# volume_board_MUSE.net
KiCad netlist of a schematic drawn in EAGLE
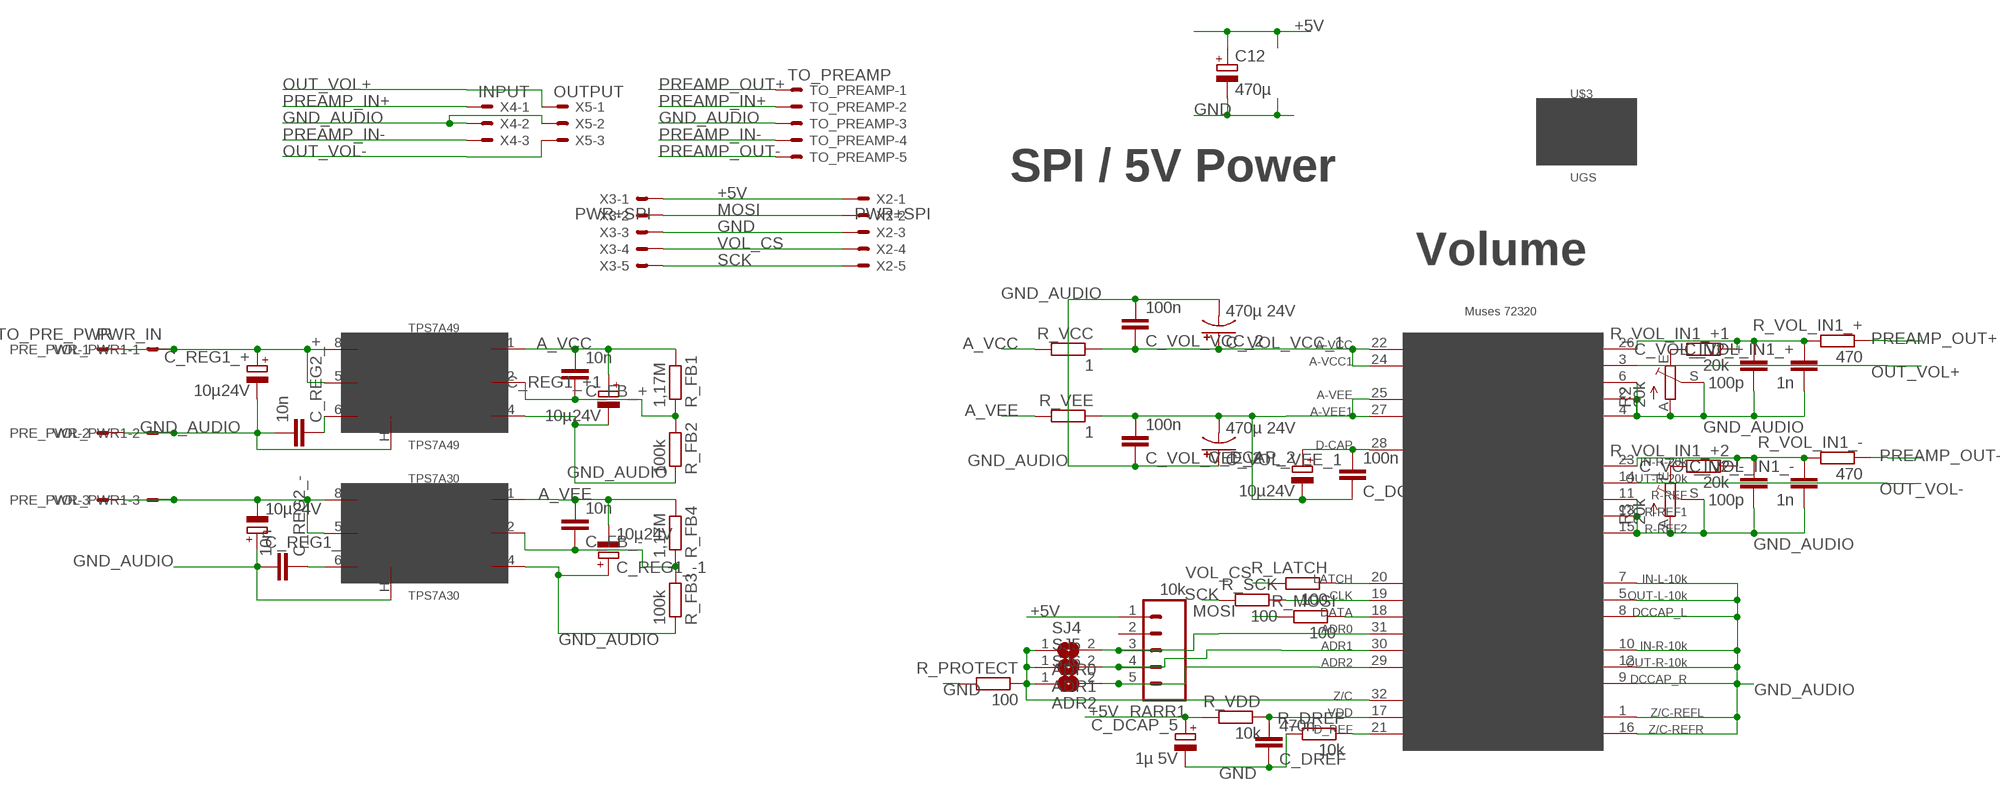
[diagram p0: schematic, sheet 1]

(export (version "E")
  (design (tool "Eeschema 10.0.6"))
  (components
    (comp (ref "C12")
      (value "470µ")
      (footprint "eagle-import:E2,5-6")
      (libsource (lib "eagle-import") (part "CPOL-EUE2.5-6"))
    )
    (comp (ref "C_DCAP_1")
      (value "100n")
      (footprint "eagle-import:C0603")
      (libsource (lib "eagle-import") (part "C-EUC0603"))
    )
    (comp (ref "C_DCAP_2")
      (value "10µ24V")
      (footprint "eagle-import:PANASONIC_C")
      (libsource (lib "eagle-import") (part "CPOL-EUC"))
    )
    (comp (ref "C_DCAP_5")
      (value "1µ 5V")
      (footprint "eagle-import:E1,8-4")
      (libsource (lib "eagle-import") (part "CPOL-EUE1.8-4"))
    )
    (comp (ref "C_DREF")
      (value "470n")
      (footprint "eagle-import:C075-042X103")
      (libsource (lib "eagle-import") (part "C-EU075-042X103"))
    )
    (comp (ref "C_FB_+")
      (value "10n")
      (footprint "eagle-import:C0603")
      (libsource (lib "eagle-import") (part "C-EUC0603"))
    )
    (comp (ref "C_FB_-")
      (value "10n")
      (footprint "eagle-import:C0603")
      (libsource (lib "eagle-import") (part "C-EUC0603"))
    )
    (comp (ref "C_REG1_+")
      (value "10µ24V")
      (footprint "eagle-import:PANASONIC_C")
      (libsource (lib "eagle-import") (part "CPOL-EUC"))
    )
    (comp (ref "C_REG1_+1")
      (value "10µ24V")
      (footprint "eagle-import:PANASONIC_C")
      (libsource (lib "eagle-import") (part "CPOL-EUC"))
    )
    (comp (ref "C_REG1_-")
      (value "10µ24V")
      (footprint "eagle-import:PANASONIC_C")
      (libsource (lib "eagle-import") (part "CPOL-EUC"))
    )
    (comp (ref "C_REG1_-1")
      (value "10µ24V")
      (footprint "eagle-import:PANASONIC_C")
      (libsource (lib "eagle-import") (part "CPOL-EUC"))
    )
    (comp (ref "C_REG2_+")
      (value "10n")
      (footprint "eagle-import:C0603")
      (libsource (lib "eagle-import") (part "C-EUC0603"))
    )
    (comp (ref "C_REG2_-")
      (value "10n")
      (footprint "eagle-import:C0603")
      (libsource (lib "eagle-import") (part "C-EUC0603"))
    )
    (comp (ref "C_VOL_IN1_+")
      (value "1n")
      (footprint "eagle-import:C102-043X133")
      (libsource (lib "eagle-import") (part "C-EU102-043X133"))
    )
    (comp (ref "C_VOL_IN1_-")
      (value "1n")
      (footprint "eagle-import:C102-043X133")
      (libsource (lib "eagle-import") (part "C-EU102-043X133"))
    )
    (comp (ref "C_VOL_IN2_+")
      (value "100p")
      (footprint "eagle-import:C075-032X103")
      (libsource (lib "eagle-import") (part "C-EU075-032X103"))
    )
    (comp (ref "C_VOL_IN2_-")
      (value "100p")
      (footprint "eagle-import:C075-032X103")
      (libsource (lib "eagle-import") (part "C-EU075-032X103"))
    )
    (comp (ref "C_VOL_VCC_1")
      (value "470µ 24V")
      (footprint "eagle-import:PANASONIC_H13")
      (libsource (lib "eagle-import") (part "CAP_POLH13"))
    )
    (comp (ref "C_VOL_VCC_2")
      (value "100n")
      (footprint "eagle-import:C0603")
      (libsource (lib "eagle-import") (part "C-EUC0603"))
    )
    (comp (ref "C_VOL_VEE_1")
      (value "470µ 24V")
      (footprint "eagle-import:PANASONIC_H13")
      (libsource (lib "eagle-import") (part "CAP_POLH13"))
    )
    (comp (ref "C_VOL_VEE_2")
      (value "100n")
      (footprint "eagle-import:C0603")
      (libsource (lib "eagle-import") (part "C-EUC0603"))
    )
    (comp (ref "PRE_PWR")
      (value "TO_PRE_PWR")
      (footprint "eagle-import:70543-03")
      (libsource (lib "eagle-import") (part "C-GRID-03-70543"))
    )
    (comp (ref "R2")
      (value "20k")
      (footprint "eagle-import:RJ9W")
      (libsource (lib "eagle-import") (part "TRIM_EU-RJ9W"))
    )
    (comp (ref "R3")
      (value "20k")
      (footprint "eagle-import:RJ9W")
      (libsource (lib "eagle-import") (part "TRIM_EU-RJ9W"))
    )
    (comp (ref "RARR1")
      (value "10k")
      (footprint "eagle-import:1X05")
      (libsource (lib "eagle-import") (part "M05PTH"))
    )
    (comp (ref "R_DREF")
      (value "10k")
      (footprint "eagle-import:0207_7")
      (libsource (lib "eagle-import") (part "R-EU_0207/7"))
    )
    (comp (ref "R_FB1")
      (value "1,17M")
      (footprint "eagle-import:0207_7")
      (libsource (lib "eagle-import") (part "R-EU_0207/7"))
    )
    (comp (ref "R_FB2")
      (value "100k")
      (footprint "eagle-import:0207_7")
      (libsource (lib "eagle-import") (part "R-EU_0207/7"))
    )
    (comp (ref "R_FB3")
      (value "100k")
      (footprint "eagle-import:0207_7")
      (libsource (lib "eagle-import") (part "R-EU_0207/7"))
    )
    (comp (ref "R_FB4")
      (value "1,17M")
      (footprint "eagle-import:0207_7")
      (libsource (lib "eagle-import") (part "R-EU_0207/7"))
    )
    (comp (ref "R_LATCH")
      (value "100")
      (footprint "eagle-import:0207_7")
      (libsource (lib "eagle-import") (part "R-EU_0207/7"))
    )
    (comp (ref "R_MOSI")
      (value "100")
      (footprint "eagle-import:0207_7")
      (libsource (lib "eagle-import") (part "R-EU_0207/7"))
    )
    (comp (ref "R_PROTECT")
      (value "100")
      (footprint "eagle-import:0207_7")
      (libsource (lib "eagle-import") (part "R-EU_0207/7"))
    )
    (comp (ref "R_SCK")
      (value "100")
      (footprint "eagle-import:0207_7")
      (libsource (lib "eagle-import") (part "R-EU_0207/7"))
    )
    (comp (ref "R_VCC")
      (value "1")
      (footprint "eagle-import:0207_7")
      (libsource (lib "eagle-import") (part "R-EU_0207/7"))
    )
    (comp (ref "R_VDD")
      (value "10k")
      (footprint "eagle-import:0207_7")
      (libsource (lib "eagle-import") (part "R-EU_0207/7"))
    )
    (comp (ref "R_VEE")
      (value "1")
      (footprint "eagle-import:0207_7")
      (libsource (lib "eagle-import") (part "R-EU_0207/7"))
    )
    (comp (ref "R_VOL_IN1_+")
      (value "470")
      (footprint "eagle-import:0207_10")
      (libsource (lib "eagle-import") (part "R-EU_0207/10"))
    )
    (comp (ref "R_VOL_IN1_+1")
      (value "20k")
      (footprint "eagle-import:0207_7")
      (libsource (lib "eagle-import") (part "R-EU_0207/7"))
    )
    (comp (ref "R_VOL_IN1_+2")
      (value "20k")
      (footprint "eagle-import:0207_7")
      (libsource (lib "eagle-import") (part "R-EU_0207/7"))
    )
    (comp (ref "R_VOL_IN1_-")
      (value "470")
      (footprint "eagle-import:0207_10")
      (libsource (lib "eagle-import") (part "R-EU_0207/10"))
    )
    (comp (ref "SJ4")
      (value "ADR0")
      (footprint "eagle-import:SJ")
      (libsource (lib "eagle-import") (part "SJ"))
    )
    (comp (ref "SJ5")
      (value "ADR1")
      (footprint "eagle-import:SJ")
      (libsource (lib "eagle-import") (part "SJ"))
    )
    (comp (ref "SJ6")
      (value "ADR2")
      (footprint "eagle-import:SJ")
      (libsource (lib "eagle-import") (part "SJ"))
    )
    (comp (ref "TO_PREAMP")
      (value "TO_PREAMP")
      (footprint "eagle-import:70543-05")
      (libsource (lib "eagle-import") (part "C-GRID-05-70543"))
    )
    (comp (ref "TPS7A30")
      (value "TPS7A30")
      (footprint "eagle-import:MSOP8")
      (libsource (lib "eagle-import") (part "TPS7A49+36V150MA_REG"))
    )
    (comp (ref "TPS7A49")
      (value "TPS7A49")
      (footprint "eagle-import:MSOP8")
      (libsource (lib "eagle-import") (part "TPS7A49+36V150MA_REG"))
    )
    (comp (ref "U$1")
      (value "MUSES72320")
      (footprint "eagle-import:SSOP32")
      (libsource (lib "eagle-import") (part "MUSES72320"))
    )
    (comp (ref "U$3")
      (value "UGS")
      (footprint "eagle-import:UGS")
      (libsource (lib "eagle-import") (part "UGS"))
    )
    (comp (ref "VOL_PWR1")
      (value "PWR_IN")
      (footprint "eagle-import:70543-03")
      (libsource (lib "eagle-import") (part "C-GRID-03-70543"))
    )
    (comp (ref "X2")
      (value "PWR+SPI")
      (footprint "eagle-import:70543-05")
      (libsource (lib "eagle-import") (part "C-GRID-05-70543"))
    )
    (comp (ref "X3")
      (value "PWR+SPI")
      (footprint "eagle-import:70543-05")
      (libsource (lib "eagle-import") (part "C-GRID-05-70543"))
    )
    (comp (ref "X4")
      (value "INPUT")
      (footprint "eagle-import:70543-03")
      (libsource (lib "eagle-import") (part "C-GRID-03-70543"))
    )
    (comp (ref "X5")
      (value "OUTPUT")
      (footprint "eagle-import:70543-03")
      (libsource (lib "eagle-import") (part "C-GRID-03-70543"))
    )
  )
  (nets
    (net (code "1") (name "/+5V") (class "Default")
      (node (ref "C12") (pin "+") (pinfunction "+_+") (pintype "passive"))
      (node (ref "C_DCAP_5") (pin "+") (pinfunction "+_+") (pintype "passive"))
      (node (ref "RARR1") (pin "1") (pinfunction "1_1") (pintype "passive"))
      (node (ref "R_VDD") (pin "2") (pinfunction "2_2") (pintype "passive"))
      (node (ref "X2") (pin "1") (pinfunction "S_1") (pintype "passive"))
      (node (ref "X3") (pin "1") (pinfunction "S_1") (pintype "passive"))
    )
    (net (code "2") (name "/A_VCC") (class "Default")
      (node (ref "C_FB_+") (pin "2") (pinfunction "2_2") (pintype "passive"))
      (node (ref "C_REG1_+1") (pin "+") (pinfunction "+_+") (pintype "passive"))
      (node (ref "R_FB1") (pin "2") (pinfunction "2_2") (pintype "passive"))
      (node (ref "R_VCC") (pin "2") (pinfunction "2_2") (pintype "passive"))
      (node (ref "TPS7A49") (pin "1") (pinfunction "OUT_1") (pintype "bidirectional"))
    )
    (net (code "3") (name "/A_VEE") (class "Default")
      (node (ref "C_FB_-") (pin "2") (pinfunction "2_2") (pintype "passive"))
      (node (ref "C_REG1_-1") (pin "-") (pinfunction "-_-") (pintype "passive"))
      (node (ref "R_FB4") (pin "2") (pinfunction "2_2") (pintype "passive"))
      (node (ref "R_VEE") (pin "2") (pinfunction "2_2") (pintype "passive"))
      (node (ref "TPS7A30") (pin "1") (pinfunction "OUT_1") (pintype "bidirectional"))
    )
    (net (code "4") (name "/GND") (class "Default")
      (node (ref "C12") (pin "-") (pinfunction "-_-") (pintype "passive"))
      (node (ref "C_DCAP_5") (pin "-") (pinfunction "-_-") (pintype "passive"))
      (node (ref "C_DREF") (pin "1") (pinfunction "1_1") (pintype "passive"))
      (node (ref "R_DREF") (pin "2") (pinfunction "2_2") (pintype "passive"))
      (node (ref "R_PROTECT") (pin "2") (pinfunction "2_2") (pintype "passive"))
      (node (ref "X2") (pin "3") (pinfunction "S_3") (pintype "passive"))
      (node (ref "X3") (pin "3") (pinfunction "S_3") (pintype "passive"))
    )
    (net (code "5") (name "/GND_AUDIO") (class "Default")
      (node (ref "C_REG1_+") (pin "-") (pinfunction "-_-") (pintype "passive"))
      (node (ref "C_REG1_+1") (pin "-") (pinfunction "-_-") (pintype "passive"))
      (node (ref "C_REG1_-") (pin "+") (pinfunction "+_+") (pintype "passive"))
      (node (ref "C_REG1_-1") (pin "+") (pinfunction "+_+") (pintype "passive"))
      (node (ref "C_REG2_+") (pin "2") (pinfunction "2_2") (pintype "passive"))
      (node (ref "C_REG2_-") (pin "2") (pinfunction "2_2") (pintype "passive"))
      (node (ref "C_VOL_IN1_+") (pin "2") (pinfunction "2_2") (pintype "passive"))
      (node (ref "C_VOL_IN1_-") (pin "2") (pinfunction "2_2") (pintype "passive"))
      (node (ref "C_VOL_IN2_+") (pin "2") (pinfunction "2_2") (pintype "passive"))
      (node (ref "C_VOL_IN2_-") (pin "2") (pinfunction "2_2") (pintype "passive"))
      (node (ref "C_VOL_VCC_1") (pin "-") (pinfunction "-_-") (pintype "passive"))
      (node (ref "C_VOL_VCC_2") (pin "2") (pinfunction "2_2") (pintype "passive"))
      (node (ref "C_VOL_VEE_1") (pin "+") (pinfunction "+_+") (pintype "passive"))
      (node (ref "C_VOL_VEE_2") (pin "1") (pinfunction "1_1") (pintype "passive"))
      (node (ref "PRE_PWR") (pin "2") (pinfunction "S_2") (pintype "passive"))
      (node (ref "R2") (pin "A") (pinfunction "A_A") (pintype "passive"))
      (node (ref "R2") (pin "S") (pinfunction "S_S") (pintype "passive"))
      (node (ref "R3") (pin "A") (pinfunction "A_A") (pintype "passive"))
      (node (ref "R3") (pin "S") (pinfunction "S_S") (pintype "passive"))
      (node (ref "R_FB2") (pin "1") (pinfunction "1_1") (pintype "passive"))
      (node (ref "R_FB3") (pin "1") (pinfunction "1_1") (pintype "passive"))
      (node (ref "TO_PREAMP") (pin "3") (pinfunction "S_3") (pintype "passive"))
      (node (ref "TPS7A30") (pin "4") (pinfunction "GND_4") (pintype "bidirectional"))
      (node (ref "TPS7A30") (pin "H") (pinfunction "H_H") (pintype "bidirectional"))
      (node (ref "TPS7A49") (pin "4") (pinfunction "GND_4") (pintype "bidirectional"))
      (node (ref "TPS7A49") (pin "H") (pinfunction "H_H") (pintype "bidirectional"))
      (node (ref "U$1") (pin "1") (pinfunction "P$1_1") (pintype "bidirectional"))
      (node (ref "U$1") (pin "10") (pinfunction "P$10_10") (pintype "bidirectional"))
      (node (ref "U$1") (pin "11") (pinfunction "P$11_11") (pintype "bidirectional"))
      (node (ref "U$1") (pin "12") (pinfunction "P$12_12") (pintype "bidirectional"))
      (node (ref "U$1") (pin "13") (pinfunction "P$13_13") (pintype "bidirectional"))
      (node (ref "U$1") (pin "15") (pinfunction "P$15_15") (pintype "bidirectional"))
      (node (ref "U$1") (pin "16") (pinfunction "P$16_16") (pintype "bidirectional"))
      (node (ref "U$1") (pin "2") (pinfunction "P$2_2") (pintype "bidirectional"))
      (node (ref "U$1") (pin "4") (pinfunction "P$4_4") (pintype "bidirectional"))
      (node (ref "U$1") (pin "5") (pinfunction "P$5_5") (pintype "bidirectional"))
      (node (ref "U$1") (pin "6") (pinfunction "P$6_6") (pintype "bidirectional"))
      (node (ref "U$1") (pin "7") (pinfunction "P$7_7") (pintype "bidirectional"))
      (node (ref "U$1") (pin "8") (pinfunction "P$8_8") (pintype "bidirectional"))
      (node (ref "U$1") (pin "9") (pinfunction "P$9_9") (pintype "bidirectional"))
      (node (ref "VOL_PWR1") (pin "2") (pinfunction "S_2") (pintype "passive"))
      (node (ref "X4") (pin "2") (pinfunction "S_2") (pintype "passive"))
      (node (ref "X5") (pin "2") (pinfunction "S_2") (pintype "passive"))
    )
    (net (code "6") (name "/MOSI") (class "Default")
      (node (ref "R_MOSI") (pin "2") (pinfunction "2_2") (pintype "passive"))
      (node (ref "X2") (pin "2") (pinfunction "S_2") (pintype "passive"))
      (node (ref "X3") (pin "2") (pinfunction "S_2") (pintype "passive"))
    )
    (net (code "7") (name "/OUT_VOL+") (class "Default")
      (node (ref "U$1") (pin "3") (pinfunction "P$3_3") (pintype "bidirectional"))
      (node (ref "X5") (pin "1") (pinfunction "S_1") (pintype "passive"))
    )
    (net (code "8") (name "/OUT_VOL-") (class "Default")
      (node (ref "U$1") (pin "14") (pinfunction "P$14_14") (pintype "bidirectional"))
      (node (ref "X5") (pin "3") (pinfunction "S_3") (pintype "passive"))
    )
    (net (code "9") (name "/PREAMP_IN+") (class "Default")
      (node (ref "TO_PREAMP") (pin "2") (pinfunction "S_2") (pintype "passive"))
      (node (ref "X4") (pin "1") (pinfunction "S_1") (pintype "passive"))
    )
    (net (code "10") (name "/PREAMP_IN-") (class "Default")
      (node (ref "TO_PREAMP") (pin "4") (pinfunction "S_4") (pintype "passive"))
      (node (ref "X4") (pin "3") (pinfunction "S_3") (pintype "passive"))
    )
    (net (code "11") (name "/PREAMP_OUT+") (class "Default")
      (node (ref "R_VOL_IN1_+") (pin "1") (pinfunction "1_1") (pintype "passive"))
      (node (ref "TO_PREAMP") (pin "1") (pinfunction "S_1") (pintype "passive"))
    )
    (net (code "12") (name "/PREAMP_OUT-") (class "Default")
      (node (ref "R_VOL_IN1_-") (pin "1") (pinfunction "1_1") (pintype "passive"))
      (node (ref "TO_PREAMP") (pin "5") (pinfunction "S_5") (pintype "passive"))
    )
    (net (code "13") (name "/SCK") (class "Default")
      (node (ref "R_SCK") (pin "2") (pinfunction "2_2") (pintype "passive"))
      (node (ref "X2") (pin "5") (pinfunction "S_5") (pintype "passive"))
      (node (ref "X3") (pin "5") (pinfunction "S_5") (pintype "passive"))
    )
    (net (code "14") (name "/VOL_CS") (class "Default")
      (node (ref "R_LATCH") (pin "2") (pinfunction "2_2") (pintype "passive"))
      (node (ref "X2") (pin "4") (pinfunction "S_4") (pintype "passive"))
      (node (ref "X3") (pin "4") (pinfunction "S_4") (pintype "passive"))
    )
    (net (code "15") (name "Net-(PRE_PWRA-S)") (class "Default")
      (node (ref "C_REG1_+") (pin "+") (pinfunction "+_+") (pintype "passive"))
      (node (ref "PRE_PWR") (pin "1") (pinfunction "S_1") (pintype "passive"))
      (node (ref "TPS7A49") (pin "5") (pinfunction "EN_5") (pintype "bidirectional"))
      (node (ref "TPS7A49") (pin "8") (pinfunction "IN_8") (pintype "bidirectional"))
      (node (ref "VOL_PWR1") (pin "1") (pinfunction "S_1") (pintype "passive"))
    )
    (net (code "16") (name "Net-(PRE_PWRC-S)") (class "Default")
      (node (ref "C_REG1_-") (pin "-") (pinfunction "-_-") (pintype "passive"))
      (node (ref "PRE_PWR") (pin "3") (pinfunction "S_3") (pintype "passive"))
      (node (ref "TPS7A30") (pin "5") (pinfunction "EN_5") (pintype "bidirectional"))
      (node (ref "TPS7A30") (pin "8") (pinfunction "IN_8") (pintype "bidirectional"))
      (node (ref "VOL_PWR1") (pin "3") (pinfunction "S_3") (pintype "passive"))
    )
    (net (code "17") (name "Net-(R2-PadE)") (class "Default")
      (node (ref "R2") (pin "E") (pinfunction "E_E") (pintype "passive"))
      (node (ref "R_VOL_IN1_+1") (pin "2") (pinfunction "2_2") (pintype "passive"))
    )
    (net (code "18") (name "Net-(R3-PadE)") (class "Default")
      (node (ref "R3") (pin "E") (pinfunction "E_E") (pintype "passive"))
      (node (ref "R_VOL_IN1_+2") (pin "2") (pinfunction "2_2") (pintype "passive"))
    )
    (net (code "19") (name "Net-(TPS7A30-FB)") (class "Default")
      (node (ref "C_FB_-") (pin "1") (pinfunction "1_1") (pintype "passive"))
      (node (ref "R_FB3") (pin "2") (pinfunction "2_2") (pintype "passive"))
      (node (ref "R_FB4") (pin "1") (pinfunction "1_1") (pintype "passive"))
      (node (ref "TPS7A30") (pin "2") (pinfunction "FB_2") (pintype "bidirectional"))
    )
    (net (code "20") (name "Net-(TPS7A30-NR{slash}SS)") (class "Default")
      (node (ref "C_REG2_-") (pin "1") (pinfunction "1_1") (pintype "passive"))
      (node (ref "TPS7A30") (pin "6") (pinfunction "NR/SS_6") (pintype "bidirectional"))
    )
    (net (code "21") (name "Net-(TPS7A49-FB)") (class "Default")
      (node (ref "C_FB_+") (pin "1") (pinfunction "1_1") (pintype "passive"))
      (node (ref "R_FB1") (pin "1") (pinfunction "1_1") (pintype "passive"))
      (node (ref "R_FB2") (pin "2") (pinfunction "2_2") (pintype "passive"))
      (node (ref "TPS7A49") (pin "2") (pinfunction "FB_2") (pintype "bidirectional"))
    )
    (net (code "22") (name "Net-(TPS7A49-NR{slash}SS)") (class "Default")
      (node (ref "C_REG2_+") (pin "1") (pinfunction "1_1") (pintype "passive"))
      (node (ref "TPS7A49") (pin "6") (pinfunction "NR/SS_6") (pintype "bidirectional"))
    )
    (net (code "23") (name "Net-(U$1-P$17)") (class "Default")
      (node (ref "C_DREF") (pin "2") (pinfunction "2_2") (pintype "passive"))
      (node (ref "R_VDD") (pin "1") (pinfunction "1_1") (pintype "passive"))
      (node (ref "U$1") (pin "17") (pinfunction "P$17_17") (pintype "bidirectional"))
    )
    (net (code "24") (name "Net-(U$1-P$18)") (class "Default")
      (node (ref "R_MOSI") (pin "1") (pinfunction "1_1") (pintype "passive"))
      (node (ref "U$1") (pin "18") (pinfunction "P$18_18") (pintype "bidirectional"))
    )
    (net (code "25") (name "Net-(U$1-P$19)") (class "Default")
      (node (ref "R_SCK") (pin "1") (pinfunction "1_1") (pintype "passive"))
      (node (ref "U$1") (pin "19") (pinfunction "P$19_19") (pintype "bidirectional"))
    )
    (net (code "26") (name "Net-(U$1-P$20)") (class "Default")
      (node (ref "R_LATCH") (pin "1") (pinfunction "1_1") (pintype "passive"))
      (node (ref "U$1") (pin "20") (pinfunction "P$20_20") (pintype "bidirectional"))
    )
    (net (code "27") (name "Net-(U$1-P$21)") (class "Default")
      (node (ref "R_DREF") (pin "1") (pinfunction "1_1") (pintype "passive"))
      (node (ref "U$1") (pin "21") (pinfunction "P$21_21") (pintype "bidirectional"))
    )
    (net (code "28") (name "Net-(U$1-P$22)") (class "Default")
      (node (ref "C_VOL_VCC_1") (pin "+") (pinfunction "+_+") (pintype "passive"))
      (node (ref "C_VOL_VCC_2") (pin "1") (pinfunction "1_1") (pintype "passive"))
      (node (ref "R_VCC") (pin "1") (pinfunction "1_1") (pintype "passive"))
      (node (ref "U$1") (pin "22") (pinfunction "P$22_22") (pintype "bidirectional"))
      (node (ref "U$1") (pin "24") (pinfunction "P$24_24") (pintype "bidirectional"))
    )
    (net (code "29") (name "Net-(U$1-P$23)") (class "Default")
      (node (ref "C_VOL_IN1_-") (pin "1") (pinfunction "1_1") (pintype "passive"))
      (node (ref "C_VOL_IN2_-") (pin "1") (pinfunction "1_1") (pintype "passive"))
      (node (ref "R_VOL_IN1_+2") (pin "1") (pinfunction "1_1") (pintype "passive"))
      (node (ref "R_VOL_IN1_-") (pin "2") (pinfunction "2_2") (pintype "passive"))
      (node (ref "U$1") (pin "23") (pinfunction "P$23_23") (pintype "bidirectional"))
    )
    (net (code "30") (name "Net-(U$1-P$25)") (class "Default")
      (node (ref "C_DCAP_1") (pin "1") (pinfunction "1_1") (pintype "passive"))
      (node (ref "C_DCAP_2") (pin "-") (pinfunction "-_-") (pintype "passive"))
      (node (ref "C_VOL_VEE_1") (pin "-") (pinfunction "-_-") (pintype "passive"))
      (node (ref "C_VOL_VEE_2") (pin "2") (pinfunction "2_2") (pintype "passive"))
      (node (ref "R_VEE") (pin "1") (pinfunction "1_1") (pintype "passive"))
      (node (ref "U$1") (pin "25") (pinfunction "P$25_25") (pintype "bidirectional"))
      (node (ref "U$1") (pin "27") (pinfunction "P$27_27") (pintype "bidirectional"))
    )
    (net (code "31") (name "Net-(U$1-P$26)") (class "Default")
      (node (ref "C_VOL_IN1_+") (pin "1") (pinfunction "1_1") (pintype "passive"))
      (node (ref "C_VOL_IN2_+") (pin "1") (pinfunction "1_1") (pintype "passive"))
      (node (ref "R_VOL_IN1_+") (pin "2") (pinfunction "2_2") (pintype "passive"))
      (node (ref "R_VOL_IN1_+1") (pin "1") (pinfunction "1_1") (pintype "passive"))
      (node (ref "U$1") (pin "26") (pinfunction "P$26_26") (pintype "bidirectional"))
    )
    (net (code "32") (name "Net-(U$1-P$28)") (class "Default")
      (node (ref "C_DCAP_1") (pin "2") (pinfunction "2_2") (pintype "passive"))
      (node (ref "C_DCAP_2") (pin "+") (pinfunction "+_+") (pintype "passive"))
      (node (ref "U$1") (pin "28") (pinfunction "P$28_28") (pintype "bidirectional"))
    )
    (net (code "33") (name "Net-(U$1-P$29)") (class "Default")
      (node (ref "RARR1") (pin "5") (pinfunction "5_5") (pintype "passive"))
      (node (ref "SJ6") (pin "2") (pinfunction "2_2") (pintype "passive"))
      (node (ref "U$1") (pin "29") (pinfunction "P$29_29") (pintype "bidirectional"))
    )
    (net (code "34") (name "Net-(U$1-P$30)") (class "Default")
      (node (ref "RARR1") (pin "4") (pinfunction "4_4") (pintype "passive"))
      (node (ref "SJ5") (pin "2") (pinfunction "2_2") (pintype "passive"))
      (node (ref "U$1") (pin "30") (pinfunction "P$30_30") (pintype "bidirectional"))
    )
    (net (code "35") (name "Net-(U$1-P$31)") (class "Default")
      (node (ref "RARR1") (pin "3") (pinfunction "3_3") (pintype "passive"))
      (node (ref "SJ4") (pin "2") (pinfunction "2_2") (pintype "passive"))
      (node (ref "U$1") (pin "31") (pinfunction "P$31_31") (pintype "bidirectional"))
    )
    (net (code "36") (name "Net-(U$1-P$32)") (class "Default")
      (node (ref "R_PROTECT") (pin "1") (pinfunction "1_1") (pintype "passive"))
      (node (ref "SJ4") (pin "1") (pinfunction "1_1") (pintype "passive"))
      (node (ref "SJ5") (pin "1") (pinfunction "1_1") (pintype "passive"))
      (node (ref "SJ6") (pin "1") (pinfunction "1_1") (pintype "passive"))
      (node (ref "U$1") (pin "32") (pinfunction "P$32_32") (pintype "bidirectional"))
    )
    (net (code "37") (name "unconnected-(RARR1-Pad2)") (class "Default")
      (node (ref "RARR1") (pin "2") (pinfunction "2_2") (pintype "passive"))
    )
  )
)
